# canDrive_hw_board1_v2.net
KiCad netlist of a schematic drawn in Altium Designer
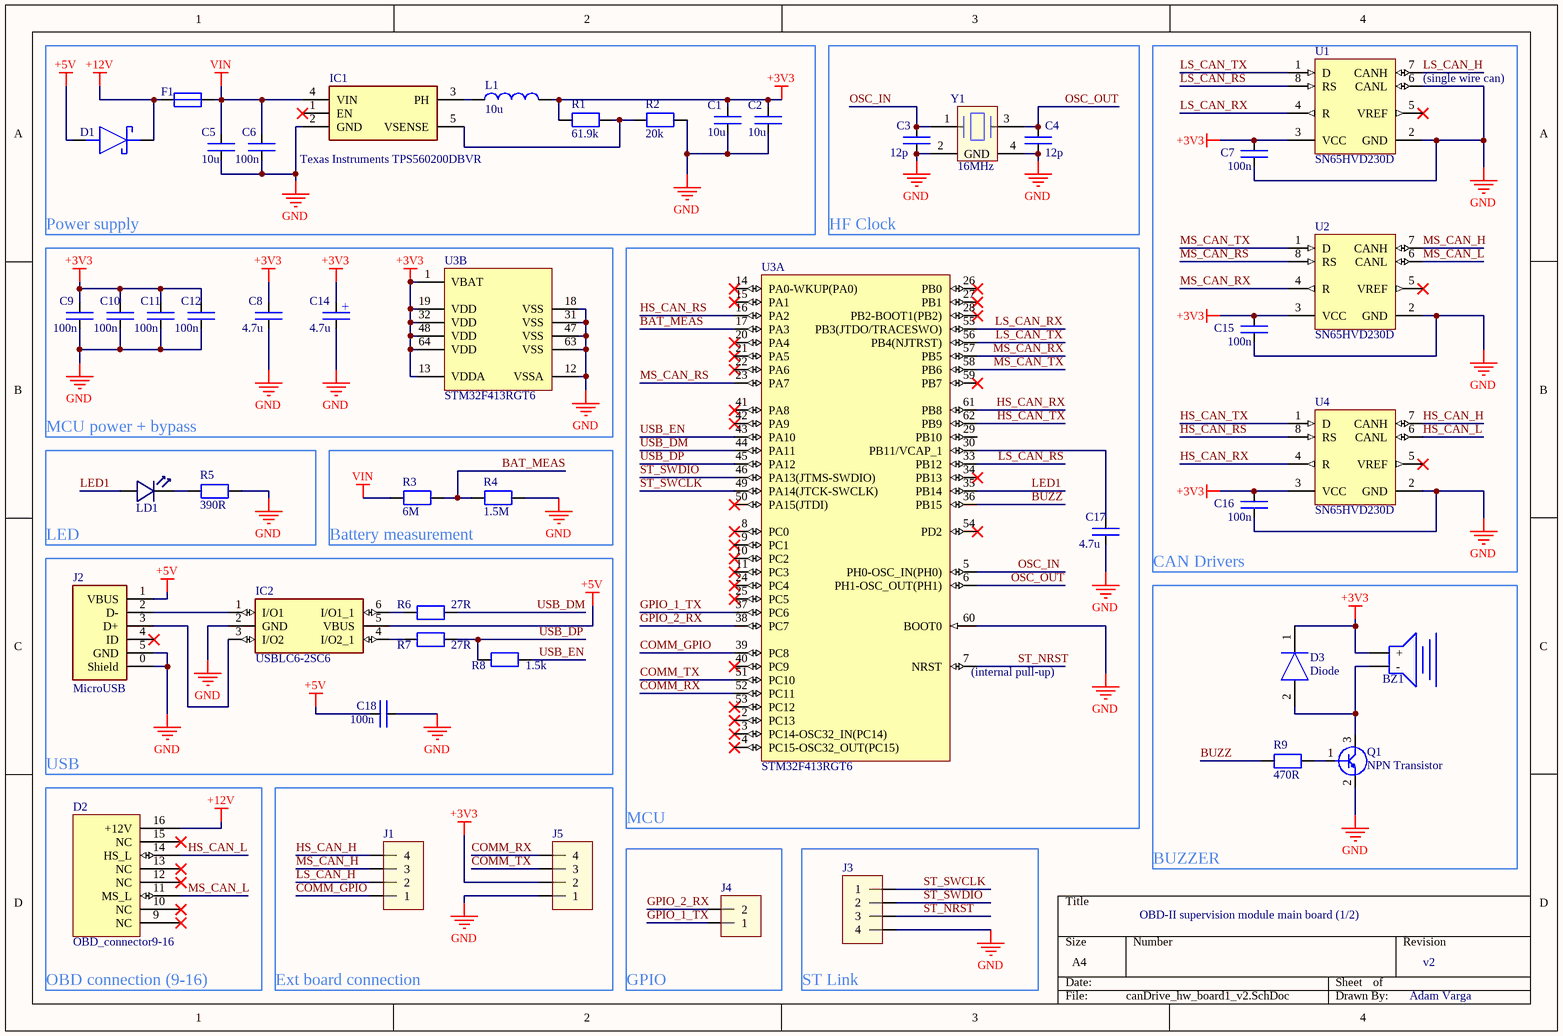
[diagram p0: canDrive_hw_board1_v2.SchDoc]

(export (version "E")
  (design (tool "Eeschema 10.0.6"))
  (components
    (comp (ref "BZ1")
      (value "Buzzer")
      (footprint "52x52_buzzer")
      (libsource (lib "canDrive_comp_sch_lib") (part "Buzzer"))
    )
    (comp (ref "C1")
      (value "10u")
      (footprint "C0603")
      (description "Capacitor")
      (libsource (lib "canDrive_comp_sch_lib") (part "Capacitor"))
    )
    (comp (ref "C2")
      (value "10u")
      (footprint "C0603")
      (description "Capacitor")
      (libsource (lib "canDrive_comp_sch_lib") (part "Capacitor"))
    )
    (comp (ref "C3")
      (value "12p")
      (footprint "C0603")
      (description "Capacitor")
      (libsource (lib "canDrive_comp_sch_lib") (part "Capacitor"))
    )
    (comp (ref "C4")
      (value "12p")
      (footprint "C0603")
      (description "Capacitor")
      (libsource (lib "canDrive_comp_sch_lib") (part "Capacitor"))
    )
    (comp (ref "C5")
      (value "10u")
      (footprint "C0603")
      (description "Capacitor")
      (libsource (lib "canDrive_comp_sch_lib") (part "Capacitor"))
    )
    (comp (ref "C6")
      (value "100n")
      (footprint "C0603")
      (description "Capacitor")
      (fields (field (name "PART") "C119027"))
      (libsource (lib "canDrive_comp_sch_lib") (part "Capacitor"))
    )
    (comp (ref "C7")
      (value "100n")
      (footprint "C0603")
      (description "Capacitor")
      (libsource (lib "canDrive_comp_sch_lib") (part "Capacitor"))
    )
    (comp (ref "C8")
      (value "4.7u")
      (footprint "C0603")
      (description "Capacitor")
      (libsource (lib "canDrive_comp_sch_lib") (part "Capacitor"))
    )
    (comp (ref "C9")
      (value "100n")
      (footprint "C0603")
      (description "Capacitor")
      (libsource (lib "canDrive_comp_sch_lib") (part "Capacitor"))
    )
    (comp (ref "C10")
      (value "100n")
      (footprint "C0603")
      (description "Capacitor")
      (libsource (lib "canDrive_comp_sch_lib") (part "Capacitor"))
    )
    (comp (ref "C11")
      (value "100n")
      (footprint "C0603")
      (description "Capacitor")
      (libsource (lib "canDrive_comp_sch_lib") (part "Capacitor"))
    )
    (comp (ref "C12")
      (value "100n")
      (footprint "C0603")
      (description "Capacitor")
      (libsource (lib "canDrive_comp_sch_lib") (part "Capacitor"))
    )
    (comp (ref "C14")
      (value "4.7u")
      (footprint "CAP3216X180N_polar")
      (description "Capacitor")
      (fields (field (name "Comment") "Capacitor_polarized"))
      (libsource (lib "canDrive_comp_sch_lib") (part "Capacitor_polarized"))
    )
    (comp (ref "C15")
      (value "100n")
      (footprint "C0603")
      (description "Capacitor")
      (libsource (lib "canDrive_comp_sch_lib") (part "Capacitor"))
    )
    (comp (ref "C16")
      (value "100n")
      (footprint "C0603")
      (description "Capacitor")
      (libsource (lib "canDrive_comp_sch_lib") (part "Capacitor"))
    )
    (comp (ref "C17")
      (value "4.7u")
      (footprint "C0603")
      (description "Capacitor")
      (libsource (lib "canDrive_comp_sch_lib") (part "Capacitor"))
    )
    (comp (ref "C18")
      (value "100n")
      (footprint "C0603")
      (description "Capacitor")
      (libsource (lib "canDrive_comp_sch_lib") (part "Capacitor"))
    )
    (comp (ref "D1")
      (value "~")
      (footprint "SODFL3516X120N")
      (description "Schottky Diode")
      (libsource (lib "canDrive_comp_sch_lib") (part "PMEG4005EH,115"))
    )
    (comp (ref "D2")
      (value "OBD_connector9-16")
      (footprint "OBD9-16")
      (libsource (lib "canDrive_comp_sch_lib") (part "OBD9-16"))
    )
    (comp (ref "D3")
      (value "Diode")
      (footprint "CD0603S01575")
      (libsource (lib "canDrive_comp_sch_lib") (part "Diode"))
    )
    (comp (ref "F1")
      (value "~")
      (footprint "FUSE 1206")
      (libsource (lib "canDrive_comp_sch_lib") (part "Fuse"))
    )
    (comp (ref "IC1")
      (value "~")
      (footprint "SOT95P280X145-5N")
      (description "Integrated Circuit")
      (fields (field (name "NAME") "Texas Instruments TPS560200DBVR"))
      (libsource (lib "canDrive_comp_sch_lib") (part "TPS560200DBVR"))
    )
    (comp (ref "IC2")
      (value "USBLC6-2SC6")
      (footprint "SOT95P280X145-6N")
      (description "Integrated Circuit")
      (libsource (lib "canDrive_comp_sch_lib") (part "USBLC6-2SC6"))
    )
    (comp (ref "J1")
      (value "CON_1x4")
      (footprint "127mm_header_4pin")
      (description "1x4 connector")
      (libsource (lib "canDrive_comp_sch_lib") (part "CON_1x4"))
    )
    (comp (ref "J2")
      (value "micro_usb_female")
      (footprint "micro_usb")
      (libsource (lib "canDrive_comp_sch_lib") (part "micro_usb_female"))
    )
    (comp (ref "J3")
      (value "CON_1x4")
      (footprint "ribbon4pin")
      (description "1x4 connector")
      (libsource (lib "") (part "CON_1x4_1"))
    )
    (comp (ref "J4")
      (value "CON_1x2")
      (footprint "ribbon2pin")
      (description "1x4 connector")
      (libsource (lib "canDrive_comp_sch_lib") (part "CON_1x2"))
    )
    (comp (ref "J5")
      (value "CON_1x4")
      (footprint "127mm_header_4pin")
      (description "1x4 connector")
      (libsource (lib "canDrive_comp_sch_lib") (part "CON_1x4"))
    )
    (comp (ref "L1")
      (value "10u")
      (footprint "inductor")
      (fields (field (name "Comment") "Inductor"))
      (libsource (lib "canDrive_comp_sch_lib") (part "Inductor"))
    )
    (comp (ref "LD1")
      (value "LED")
      (footprint "LED_0603")
      (libsource (lib "canDrive_comp_sch_lib") (part "LED"))
    )
    (comp (ref "Q1")
      (value "NPN Transistor")
      (footprint "SOT95P230X110-3N")
      (description "Transistor BJT NPN")
      (libsource (lib "canDrive_comp_sch_lib") (part "NPN Transistor"))
    )
    (comp (ref "R1")
      (value "61.9k")
      (footprint "R0603")
      (description "Resistor")
      (libsource (lib "canDrive_comp_sch_lib") (part "Resistor"))
    )
    (comp (ref "R2")
      (value "20k")
      (footprint "R0603")
      (description "Resistor")
      (fields (field (name "PART") "C137817"))
      (libsource (lib "canDrive_comp_sch_lib") (part "Resistor"))
    )
    (comp (ref "R3")
      (value "6M")
      (footprint "R0603")
      (description "Resistor")
      (libsource (lib "canDrive_comp_sch_lib") (part "Resistor"))
    )
    (comp (ref "R4")
      (value "1.5M")
      (footprint "R0603")
      (description "Resistor")
      (libsource (lib "canDrive_comp_sch_lib") (part "Resistor"))
    )
    (comp (ref "R5")
      (value "390R")
      (footprint "R0603")
      (description "Resistor")
      (libsource (lib "canDrive_comp_sch_lib") (part "Resistor"))
    )
    (comp (ref "R6")
      (value "27R")
      (footprint "R0603")
      (description "Resistor")
      (libsource (lib "canDrive_comp_sch_lib") (part "Resistor"))
    )
    (comp (ref "R7")
      (value "27R")
      (footprint "R0603")
      (description "Resistor")
      (libsource (lib "canDrive_comp_sch_lib") (part "Resistor"))
    )
    (comp (ref "R8")
      (value "1.5k")
      (footprint "R0603")
      (description "Resistor")
      (libsource (lib "canDrive_comp_sch_lib") (part "Resistor"))
    )
    (comp (ref "R9")
      (value "470R")
      (footprint "R0603")
      (description "Resistor")
      (libsource (lib "canDrive_comp_sch_lib") (part "Resistor"))
    )
    (comp (ref "U1")
      (value "SN65HVD230D")
      (footprint "SN65HVD230D_N")
      (description "CAN Bus Transceiver, 3.3 V, -40 to 85 degC, 8-Pin SOIC (D), Green (RoHS & no Sb/Br), Tube")
      (libsource (lib "canDrive_comp_sch_lib") (part "SN65HVD230D"))
    )
    (comp (ref "U2")
      (value "SN65HVD230D")
      (footprint "SN65HVD230D_N")
      (description "CAN Bus Transceiver, 3.3 V, -40 to 85 degC, 8-Pin SOIC (D), Green (RoHS & no Sb/Br), Tube")
      (libsource (lib "canDrive_comp_sch_lib") (part "SN65HVD230D"))
    )
    (comp (ref "U3")
      (value "STM32F413RGT6")
      (footprint "STM32F413RGT6_LQFP64_MFG")
      (fields (field (name "MANUFACTURER") "STMicroelectronics") (field (name "PARTNUMBER") "STM32F413RHT6"))
      (libsource (lib "canDrive_comp_sch_lib") (part "CMP-0243-00023-3"))
    )
    (comp (ref "U4")
      (value "SN65HVD230D")
      (footprint "SN65HVD230D_N")
      (description "CAN Bus Transceiver, 3.3 V, -40 to 85 degC, 8-Pin SOIC (D), Green (RoHS & no Sb/Br), Tube")
      (libsource (lib "canDrive_comp_sch_lib") (part "SN65HVD230D"))
    )
    (comp (ref "Y1")
      (value "16MHz")
      (footprint "25x20_osc")
      (fields (field (name "Comment") "OSC_16MHZ_25x20"))
      (libsource (lib "canDrive_comp_sch_lib") (part "OSC_16MHZ_25x20"))
    )
  )
  (nets
    (net (code "1") (name "+3V3") (class "Default")
      (node (ref "BZ1") (pin "0") (pinfunction "+_0") (pintype "passive"))
      (node (ref "C1") (pin "1") (pinfunction "1_1") (pintype "passive"))
      (node (ref "C10") (pin "1") (pinfunction "1_1") (pintype "passive"))
      (node (ref "C11") (pin "1") (pinfunction "1_1") (pintype "passive"))
      (node (ref "C12") (pin "1") (pinfunction "1_1") (pintype "passive"))
      (node (ref "C14") (pin "1") (pinfunction "1_1") (pintype "passive"))
      (node (ref "C15") (pin "1") (pinfunction "1_1") (pintype "passive"))
      (node (ref "C16") (pin "1") (pinfunction "1_1") (pintype "passive"))
      (node (ref "C2") (pin "1") (pinfunction "1_1") (pintype "passive"))
      (node (ref "C7") (pin "1") (pinfunction "1_1") (pintype "passive"))
      (node (ref "C8") (pin "1") (pinfunction "1_1") (pintype "passive"))
      (node (ref "C9") (pin "1") (pinfunction "1_1") (pintype "passive"))
      (node (ref "D3") (pin "1") (pinfunction "K_1") (pintype "passive"))
      (node (ref "J5") (pin "2") (pinfunction "2_2") (pintype "passive"))
      (node (ref "L1") (pin "2") (pinfunction "2_2") (pintype "passive"))
      (node (ref "R1") (pin "0") (pinfunction "0_0") (pintype "passive"))
      (node (ref "U1") (pin "3") (pinfunction "VCC_3") (pintype "power_in"))
      (node (ref "U2") (pin "3") (pinfunction "VCC_3") (pintype "power_in"))
      (node (ref "U3") (pin "1") (pinfunction "VBAT_1") (pintype "power_in"))
      (node (ref "U3") (pin "13") (pinfunction "VDDA_13") (pintype "power_in"))
      (node (ref "U3") (pin "19") (pinfunction "VDD_19") (pintype "power_in"))
      (node (ref "U3") (pin "32") (pinfunction "VDD_32") (pintype "power_in"))
      (node (ref "U3") (pin "48") (pinfunction "VDD_48") (pintype "power_in"))
      (node (ref "U3") (pin "64") (pinfunction "VDD_64") (pintype "power_in"))
      (node (ref "U4") (pin "3") (pinfunction "VCC_3") (pintype "power_in"))
    )
    (net (code "2") (name "+5V") (class "Default")
      (node (ref "C18") (pin "1") (pinfunction "1_1") (pintype "passive"))
      (node (ref "D1") (pin "2") (pinfunction "A_2") (pintype "passive"))
      (node (ref "IC2") (pin "5") (pinfunction "VBUS_5") (pintype "passive"))
      (node (ref "J2") (pin "1") (pinfunction "VBUS_1") (pintype "power_in"))
    )
    (net (code "3") (name "+12V") (class "Default")
      (node (ref "D1") (pin "1") (pinfunction "K_1") (pintype "passive"))
      (node (ref "D2") (pin "16") (pinfunction "+12V_16") (pintype "power_in"))
      (node (ref "F1") (pin "1") (pinfunction "1_1") (pintype "passive"))
    )
    (net (code "4") (name "/BAT_MEAS") (class "Default")
      (node (ref "R3") (pin "1") (pinfunction "1_1") (pintype "passive"))
      (node (ref "R4") (pin "0") (pinfunction "0_0") (pintype "passive"))
      (node (ref "U3") (pin "17") (pinfunction "PA3_17") (pintype "bidirectional"))
    )
    (net (code "5") (name "/BUZZ") (class "Default")
      (node (ref "R9") (pin "1") (pinfunction "1_1") (pintype "passive"))
      (node (ref "U3") (pin "36") (pinfunction "PB15_36") (pintype "bidirectional"))
    )
    (net (code "6") (name "/COMM_GPIO") (class "Default")
      (node (ref "J1") (pin "1") (pinfunction "1_1") (pintype "passive"))
      (node (ref "U3") (pin "39") (pinfunction "PC8_39") (pintype "bidirectional"))
    )
    (net (code "7") (name "/COMM_RX") (class "Default")
      (node (ref "J5") (pin "4") (pinfunction "4_4") (pintype "passive"))
      (node (ref "U3") (pin "52") (pinfunction "PC11_52") (pintype "bidirectional"))
    )
    (net (code "8") (name "/COMM_TX") (class "Default")
      (node (ref "J5") (pin "3") (pinfunction "3_3") (pintype "passive"))
      (node (ref "U3") (pin "51") (pinfunction "PC10_51") (pintype "bidirectional"))
    )
    (net (code "9") (name "/GPIO_1_TX") (class "Default")
      (node (ref "J4") (pin "1") (pinfunction "1_1") (pintype "passive"))
      (node (ref "U3") (pin "37") (pinfunction "PC6_37") (pintype "bidirectional"))
    )
    (net (code "10") (name "/GPIO_2_RX") (class "Default")
      (node (ref "J4") (pin "2") (pinfunction "2_2") (pintype "passive"))
      (node (ref "U3") (pin "38") (pinfunction "PC7_38") (pintype "bidirectional"))
    )
    (net (code "11") (name "/HS_CAN_H") (class "Default")
      (node (ref "J1") (pin "4") (pinfunction "4_4") (pintype "passive"))
      (node (ref "U4") (pin "7") (pinfunction "CANH_7") (pintype "bidirectional"))
    )
    (net (code "12") (name "/HS_CAN_L") (class "Default")
      (node (ref "D2") (pin "14") (pinfunction "HS_L_14") (pintype "bidirectional"))
      (node (ref "U4") (pin "6") (pinfunction "CANL_6") (pintype "bidirectional"))
    )
    (net (code "13") (name "/HS_CAN_RS") (class "Default")
      (node (ref "U3") (pin "16") (pinfunction "PA2_16") (pintype "bidirectional"))
      (node (ref "U4") (pin "8") (pinfunction "RS_8") (pintype "input"))
    )
    (net (code "14") (name "/HS_CAN_RX") (class "Default")
      (node (ref "U3") (pin "61") (pinfunction "PB8_61") (pintype "bidirectional"))
      (node (ref "U4") (pin "4") (pinfunction "R_4") (pintype "output"))
    )
    (net (code "15") (name "/HS_CAN_TX") (class "Default")
      (node (ref "U3") (pin "62") (pinfunction "PB9_62") (pintype "bidirectional"))
      (node (ref "U4") (pin "1") (pinfunction "D_1") (pintype "input"))
    )
    (net (code "16") (name "/LED1") (class "Default")
      (node (ref "LD1") (pin "A") (pinfunction "A_A") (pintype "passive"))
      (node (ref "U3") (pin "35") (pinfunction "PB14_35") (pintype "bidirectional"))
    )
    (net (code "17") (name "/LS_CAN_H") (class "Default")
      (node (ref "J1") (pin "2") (pinfunction "2_2") (pintype "passive"))
      (node (ref "U1") (pin "7") (pinfunction "CANH_7") (pintype "bidirectional"))
    )
    (net (code "18") (name "/LS_CAN_RS") (class "Default")
      (node (ref "U1") (pin "8") (pinfunction "RS_8") (pintype "input"))
      (node (ref "U3") (pin "33") (pinfunction "PB12_33") (pintype "bidirectional"))
    )
    (net (code "19") (name "/LS_CAN_RX") (class "Default")
      (node (ref "U1") (pin "4") (pinfunction "R_4") (pintype "output"))
      (node (ref "U3") (pin "55") (pinfunction "PB3(JTDO/TRACESWO)_55") (pintype "bidirectional"))
    )
    (net (code "20") (name "/LS_CAN_TX") (class "Default")
      (node (ref "U1") (pin "1") (pinfunction "D_1") (pintype "input"))
      (node (ref "U3") (pin "56") (pinfunction "PB4(NJTRST)_56") (pintype "bidirectional"))
    )
    (net (code "21") (name "/MS_CAN_H") (class "Default")
      (node (ref "J1") (pin "3") (pinfunction "3_3") (pintype "passive"))
      (node (ref "U2") (pin "7") (pinfunction "CANH_7") (pintype "bidirectional"))
    )
    (net (code "22") (name "/MS_CAN_L") (class "Default")
      (node (ref "D2") (pin "11") (pinfunction "MS_L_11") (pintype "bidirectional"))
      (node (ref "U2") (pin "6") (pinfunction "CANL_6") (pintype "bidirectional"))
    )
    (net (code "23") (name "/MS_CAN_RS") (class "Default")
      (node (ref "U2") (pin "8") (pinfunction "RS_8") (pintype "input"))
      (node (ref "U3") (pin "23") (pinfunction "PA7_23") (pintype "bidirectional"))
    )
    (net (code "24") (name "/MS_CAN_RX") (class "Default")
      (node (ref "U2") (pin "4") (pinfunction "R_4") (pintype "output"))
      (node (ref "U3") (pin "57") (pinfunction "PB5_57") (pintype "bidirectional"))
    )
    (net (code "25") (name "/MS_CAN_TX") (class "Default")
      (node (ref "U2") (pin "1") (pinfunction "D_1") (pintype "input"))
      (node (ref "U3") (pin "58") (pinfunction "PB6_58") (pintype "bidirectional"))
    )
    (net (code "26") (name "/OSC_IN") (class "Default")
      (node (ref "C3") (pin "1") (pinfunction "1_1") (pintype "passive"))
      (node (ref "U3") (pin "5") (pinfunction "PH0-OSC_IN(PH0)_5") (pintype "bidirectional"))
      (node (ref "Y1") (pin "1") (pinfunction "1_HOT_1") (pintype "passive"))
    )
    (net (code "27") (name "/OSC_OUT") (class "Default")
      (node (ref "C4") (pin "1") (pinfunction "1_1") (pintype "passive"))
      (node (ref "U3") (pin "6") (pinfunction "PH1-OSC_OUT(PH1)_6") (pintype "bidirectional"))
      (node (ref "Y1") (pin "3") (pinfunction "2_HOT_3") (pintype "passive"))
    )
    (net (code "28") (name "/ST_NRST") (class "Default")
      (node (ref "J3") (pin "3") (pinfunction "3_3") (pintype "passive"))
      (node (ref "U3") (pin "7") (pinfunction "NRST_7") (pintype "bidirectional"))
    )
    (net (code "29") (name "/ST_SWCLK") (class "Default")
      (node (ref "J3") (pin "1") (pinfunction "1_1") (pintype "passive"))
      (node (ref "U3") (pin "49") (pinfunction "PA14(JTCK-SWCLK)_49") (pintype "bidirectional"))
    )
    (net (code "30") (name "/ST_SWDIO") (class "Default")
      (node (ref "J3") (pin "2") (pinfunction "2_2") (pintype "passive"))
      (node (ref "U3") (pin "46") (pinfunction "PA13(JTMS-SWDIO)_46") (pintype "bidirectional"))
    )
    (net (code "31") (name "/USB_DM") (class "Default")
      (node (ref "R6") (pin "1") (pinfunction "1_1") (pintype "passive"))
      (node (ref "U3") (pin "44") (pinfunction "PA11_44") (pintype "bidirectional"))
    )
    (net (code "32") (name "/USB_DP") (class "Default")
      (node (ref "R7") (pin "1") (pinfunction "1_1") (pintype "passive"))
      (node (ref "R8") (pin "0") (pinfunction "0_0") (pintype "passive"))
      (node (ref "U3") (pin "45") (pinfunction "PA12_45") (pintype "bidirectional"))
    )
    (net (code "33") (name "/USB_EN") (class "Default")
      (node (ref "R8") (pin "1") (pinfunction "1_1") (pintype "passive"))
      (node (ref "U3") (pin "43") (pinfunction "PA10_43") (pintype "bidirectional"))
    )
    (net (code "34") (name "GND") (class "Default")
      (node (ref "C1") (pin "0") (pinfunction "0_0") (pintype "passive"))
      (node (ref "C10") (pin "0") (pinfunction "0_0") (pintype "passive"))
      (node (ref "C11") (pin "0") (pinfunction "0_0") (pintype "passive"))
      (node (ref "C12") (pin "0") (pinfunction "0_0") (pintype "passive"))
      (node (ref "C14") (pin "2") (pinfunction "2_2") (pintype "passive"))
      (node (ref "C15") (pin "0") (pinfunction "0_0") (pintype "passive"))
      (node (ref "C16") (pin "0") (pinfunction "0_0") (pintype "passive"))
      (node (ref "C17") (pin "0") (pinfunction "0_0") (pintype "passive"))
      (node (ref "C18") (pin "0") (pinfunction "0_0") (pintype "passive"))
      (node (ref "C2") (pin "0") (pinfunction "0_0") (pintype "passive"))
      (node (ref "C3") (pin "0") (pinfunction "0_0") (pintype "passive"))
      (node (ref "C4") (pin "0") (pinfunction "0_0") (pintype "passive"))
      (node (ref "C5") (pin "0") (pinfunction "0_0") (pintype "passive"))
      (node (ref "C6") (pin "0") (pinfunction "0_0") (pintype "passive"))
      (node (ref "C7") (pin "0") (pinfunction "0_0") (pintype "passive"))
      (node (ref "C8") (pin "0") (pinfunction "0_0") (pintype "passive"))
      (node (ref "C9") (pin "0") (pinfunction "0_0") (pintype "passive"))
      (node (ref "IC1") (pin "2") (pinfunction "GND_2") (pintype "passive"))
      (node (ref "IC2") (pin "2") (pinfunction "GND_2") (pintype "power_in"))
      (node (ref "J2") (pin "0") (pinfunction "Shield_0") (pintype "power_in"))
      (node (ref "J2") (pin "5") (pinfunction "GND_5") (pintype "power_in"))
      (node (ref "J3") (pin "4") (pinfunction "4_4") (pintype "passive"))
      (node (ref "J5") (pin "1") (pinfunction "1_1") (pintype "passive"))
      (node (ref "Q1") (pin "2") (pinfunction "E_2") (pintype "passive"))
      (node (ref "R2") (pin "1") (pinfunction "1_1") (pintype "passive"))
      (node (ref "R4") (pin "1") (pinfunction "1_1") (pintype "passive"))
      (node (ref "R5") (pin "0") (pinfunction "0_0") (pintype "passive"))
      (node (ref "U1") (pin "2") (pinfunction "GND_2") (pintype "power_in"))
      (node (ref "U1") (pin "6") (pinfunction "CANL_6") (pintype "bidirectional"))
      (node (ref "U2") (pin "2") (pinfunction "GND_2") (pintype "power_in"))
      (node (ref "U3") (pin "12") (pinfunction "VSSA_12") (pintype "power_in"))
      (node (ref "U3") (pin "18") (pinfunction "VSS_18") (pintype "power_in"))
      (node (ref "U3") (pin "31") (pinfunction "VSS_31") (pintype "power_in"))
      (node (ref "U3") (pin "47") (pinfunction "VSS_47") (pintype "power_in"))
      (node (ref "U3") (pin "60") (pinfunction "BOOT0_60") (pintype "input"))
      (node (ref "U3") (pin "63") (pinfunction "VSS_63") (pintype "power_in"))
      (node (ref "U4") (pin "2") (pinfunction "GND_2") (pintype "power_in"))
      (node (ref "Y1") (pin "2") (pinfunction "GND_2") (pintype "passive"))
      (node (ref "Y1") (pin "4") (pinfunction "GND_4") (pintype "passive"))
    )
    (net (code "35") (name "Net-(BZ1--)") (class "Default")
      (node (ref "BZ1") (pin "1") (pinfunction "-_1") (pintype "passive"))
      (node (ref "D3") (pin "2") (pinfunction "A_2") (pintype "passive"))
      (node (ref "Q1") (pin "3") (pinfunction "C_3") (pintype "passive"))
    )
    (net (code "36") (name "Net-(IC1-PH)") (class "Default")
      (node (ref "IC1") (pin "3") (pinfunction "PH_3") (pintype "passive"))
      (node (ref "L1") (pin "1") (pinfunction "1_1") (pintype "passive"))
    )
    (net (code "37") (name "Net-(IC1-VSENSE)") (class "Default")
      (node (ref "IC1") (pin "5") (pinfunction "VSENSE_5") (pintype "passive"))
      (node (ref "R1") (pin "1") (pinfunction "1_1") (pintype "passive"))
      (node (ref "R2") (pin "0") (pinfunction "0_0") (pintype "passive"))
    )
    (net (code "38") (name "Net-(IC2-I{slash}O1)") (class "Default")
      (node (ref "IC2") (pin "1") (pinfunction "I/O1_1") (pintype "bidirectional"))
      (node (ref "J2") (pin "2") (pinfunction "D-_2") (pintype "passive"))
    )
    (net (code "39") (name "Net-(IC2-I{slash}O1_1)") (class "Default")
      (node (ref "IC2") (pin "6") (pinfunction "I/O1_1_6") (pintype "bidirectional"))
      (node (ref "R6") (pin "0") (pinfunction "0_0") (pintype "passive"))
    )
    (net (code "40") (name "Net-(IC2-I{slash}O2)") (class "Default")
      (node (ref "IC2") (pin "3") (pinfunction "I/O2_3") (pintype "bidirectional"))
      (node (ref "J2") (pin "3") (pinfunction "D+_3") (pintype "passive"))
    )
    (net (code "41") (name "Net-(IC2-I{slash}O2_1)") (class "Default")
      (node (ref "IC2") (pin "4") (pinfunction "I/O2_1_4") (pintype "bidirectional"))
      (node (ref "R7") (pin "0") (pinfunction "0_0") (pintype "passive"))
    )
    (net (code "42") (name "Net-(LD1-PadC)") (class "Default")
      (node (ref "LD1") (pin "C") (pinfunction "C_C") (pintype "passive"))
      (node (ref "R5") (pin "1") (pinfunction "1_1") (pintype "passive"))
    )
    (net (code "43") (name "Net-(Q1-B)") (class "Default")
      (node (ref "Q1") (pin "1") (pinfunction "B_1") (pintype "passive"))
      (node (ref "R9") (pin "0") (pinfunction "0_0") (pintype "passive"))
    )
    (net (code "44") (name "Net-(U3A-PB11{slash}VCAP_1)") (class "Default")
      (node (ref "C17") (pin "1") (pinfunction "1_1") (pintype "passive"))
      (node (ref "U3") (pin "30") (pinfunction "PB11/VCAP_1_30") (pintype "bidirectional"))
    )
    (net (code "45") (name "VIN") (class "Default")
      (node (ref "C5") (pin "1") (pinfunction "1_1") (pintype "passive"))
      (node (ref "C6") (pin "1") (pinfunction "1_1") (pintype "passive"))
      (node (ref "F1") (pin "2") (pinfunction "2_2") (pintype "passive"))
      (node (ref "IC1") (pin "4") (pinfunction "VIN_4") (pintype "passive"))
      (node (ref "R3") (pin "0") (pinfunction "0_0") (pintype "passive"))
    )
    (net (code "46") (name "unconnected-(D2-NC-Pad9)") (class "Default")
      (node (ref "D2") (pin "9") (pinfunction "NC_9") (pintype "passive+no_connect"))
    )
    (net (code "47") (name "unconnected-(D2-NC-Pad10)") (class "Default")
      (node (ref "D2") (pin "10") (pinfunction "NC_10") (pintype "passive+no_connect"))
    )
    (net (code "48") (name "unconnected-(D2-NC-Pad12)") (class "Default")
      (node (ref "D2") (pin "12") (pinfunction "NC_12") (pintype "passive+no_connect"))
    )
    (net (code "49") (name "unconnected-(D2-NC-Pad13)") (class "Default")
      (node (ref "D2") (pin "13") (pinfunction "NC_13") (pintype "passive+no_connect"))
    )
    (net (code "50") (name "unconnected-(D2-NC-Pad15)") (class "Default")
      (node (ref "D2") (pin "15") (pinfunction "NC_15") (pintype "passive+no_connect"))
    )
    (net (code "51") (name "unconnected-(IC1-EN-Pad1)") (class "Default")
      (node (ref "IC1") (pin "1") (pinfunction "EN_1") (pintype "passive+no_connect"))
    )
    (net (code "52") (name "unconnected-(J2-ID-Pad4)") (class "Default")
      (node (ref "J2") (pin "4") (pinfunction "ID_4") (pintype "passive+no_connect"))
    )
    (net (code "53") (name "unconnected-(U1-VREF-Pad5)") (class "Default")
      (node (ref "U1") (pin "5") (pinfunction "VREF_5") (pintype "output+no_connect"))
    )
    (net (code "54") (name "unconnected-(U2-VREF-Pad5)") (class "Default")
      (node (ref "U2") (pin "5") (pinfunction "VREF_5") (pintype "output+no_connect"))
    )
    (net (code "55") (name "unconnected-(U3A-PA0-WKUP(PA0)-Pad14)") (class "Default")
      (node (ref "U3") (pin "14") (pinfunction "PA0-WKUP(PA0)_14") (pintype "bidirectional+no_connect"))
    )
    (net (code "56") (name "unconnected-(U3A-PA1-Pad15)") (class "Default")
      (node (ref "U3") (pin "15") (pinfunction "PA1_15") (pintype "bidirectional+no_connect"))
    )
    (net (code "57") (name "unconnected-(U3A-PA4-Pad20)") (class "Default")
      (node (ref "U3") (pin "20") (pinfunction "PA4_20") (pintype "bidirectional+no_connect"))
    )
    (net (code "58") (name "unconnected-(U3A-PA5-Pad21)") (class "Default")
      (node (ref "U3") (pin "21") (pinfunction "PA5_21") (pintype "bidirectional+no_connect"))
    )
    (net (code "59") (name "unconnected-(U3A-PA6-Pad22)") (class "Default")
      (node (ref "U3") (pin "22") (pinfunction "PA6_22") (pintype "bidirectional+no_connect"))
    )
    (net (code "60") (name "unconnected-(U3A-PA8-Pad41)") (class "Default")
      (node (ref "U3") (pin "41") (pinfunction "PA8_41") (pintype "bidirectional+no_connect"))
    )
    (net (code "61") (name "unconnected-(U3A-PA9-Pad42)") (class "Default")
      (node (ref "U3") (pin "42") (pinfunction "PA9_42") (pintype "bidirectional+no_connect"))
    )
    (net (code "62") (name "unconnected-(U3A-PA15(JTDI)-Pad50)") (class "Default")
      (node (ref "U3") (pin "50") (pinfunction "PA15(JTDI)_50") (pintype "bidirectional+no_connect"))
    )
    (net (code "63") (name "unconnected-(U3A-PB0-Pad26)") (class "Default")
      (node (ref "U3") (pin "26") (pinfunction "PB0_26") (pintype "bidirectional+no_connect"))
    )
    (net (code "64") (name "unconnected-(U3A-PB1-Pad27)") (class "Default")
      (node (ref "U3") (pin "27") (pinfunction "PB1_27") (pintype "bidirectional+no_connect"))
    )
    (net (code "65") (name "unconnected-(U3A-PB2-BOOT1(PB2)-Pad28)") (class "Default")
      (node (ref "U3") (pin "28") (pinfunction "PB2-BOOT1(PB2)_28") (pintype "bidirectional+no_connect"))
    )
    (net (code "66") (name "unconnected-(U3A-PB7-Pad59)") (class "Default")
      (node (ref "U3") (pin "59") (pinfunction "PB7_59") (pintype "bidirectional+no_connect"))
    )
    (net (code "67") (name "unconnected-(U3A-PB10-Pad29)") (class "Default")
      (node (ref "U3") (pin "29") (pinfunction "PB10_29") (pintype "bidirectional"))
    )
    (net (code "68") (name "unconnected-(U3A-PB13-Pad34)") (class "Default")
      (node (ref "U3") (pin "34") (pinfunction "PB13_34") (pintype "bidirectional+no_connect"))
    )
    (net (code "69") (name "unconnected-(U3A-PC0-Pad8)") (class "Default")
      (node (ref "U3") (pin "8") (pinfunction "PC0_8") (pintype "bidirectional+no_connect"))
    )
    (net (code "70") (name "unconnected-(U3A-PC1-Pad9)") (class "Default")
      (node (ref "U3") (pin "9") (pinfunction "PC1_9") (pintype "bidirectional+no_connect"))
    )
    (net (code "71") (name "unconnected-(U3A-PC2-Pad10)") (class "Default")
      (node (ref "U3") (pin "10") (pinfunction "PC2_10") (pintype "bidirectional+no_connect"))
    )
    (net (code "72") (name "unconnected-(U3A-PC3-Pad11)") (class "Default")
      (node (ref "U3") (pin "11") (pinfunction "PC3_11") (pintype "bidirectional+no_connect"))
    )
    (net (code "73") (name "unconnected-(U3A-PC4-Pad24)") (class "Default")
      (node (ref "U3") (pin "24") (pinfunction "PC4_24") (pintype "bidirectional+no_connect"))
    )
    (net (code "74") (name "unconnected-(U3A-PC5-Pad25)") (class "Default")
      (node (ref "U3") (pin "25") (pinfunction "PC5_25") (pintype "bidirectional+no_connect"))
    )
    (net (code "75") (name "unconnected-(U3A-PC9-Pad40)") (class "Default")
      (node (ref "U3") (pin "40") (pinfunction "PC9_40") (pintype "bidirectional+no_connect"))
    )
    (net (code "76") (name "unconnected-(U3A-PC12-Pad53)") (class "Default")
      (node (ref "U3") (pin "53") (pinfunction "PC12_53") (pintype "bidirectional+no_connect"))
    )
    (net (code "77") (name "unconnected-(U3A-PC13-Pad2)") (class "Default")
      (node (ref "U3") (pin "2") (pinfunction "PC13_2") (pintype "bidirectional+no_connect"))
    )
    (net (code "78") (name "unconnected-(U3A-PC14-OSC32_IN(PC14)-Pad3)") (class "Default")
      (node (ref "U3") (pin "3") (pinfunction "PC14-OSC32_IN(PC14)_3") (pintype "bidirectional+no_connect"))
    )
    (net (code "79") (name "unconnected-(U3A-PC15-OSC32_OUT(PC15)-Pad4)") (class "Default")
      (node (ref "U3") (pin "4") (pinfunction "PC15-OSC32_OUT(PC15)_4") (pintype "bidirectional+no_connect"))
    )
    (net (code "80") (name "unconnected-(U3A-PD2-Pad54)") (class "Default")
      (node (ref "U3") (pin "54") (pinfunction "PD2_54") (pintype "bidirectional+no_connect"))
    )
    (net (code "81") (name "unconnected-(U4-VREF-Pad5)") (class "Default")
      (node (ref "U4") (pin "5") (pinfunction "VREF_5") (pintype "output+no_connect"))
    )
  )
)
